# schematic_easyeda.net
KiCad netlist of a schematic drawn in EasyEDA
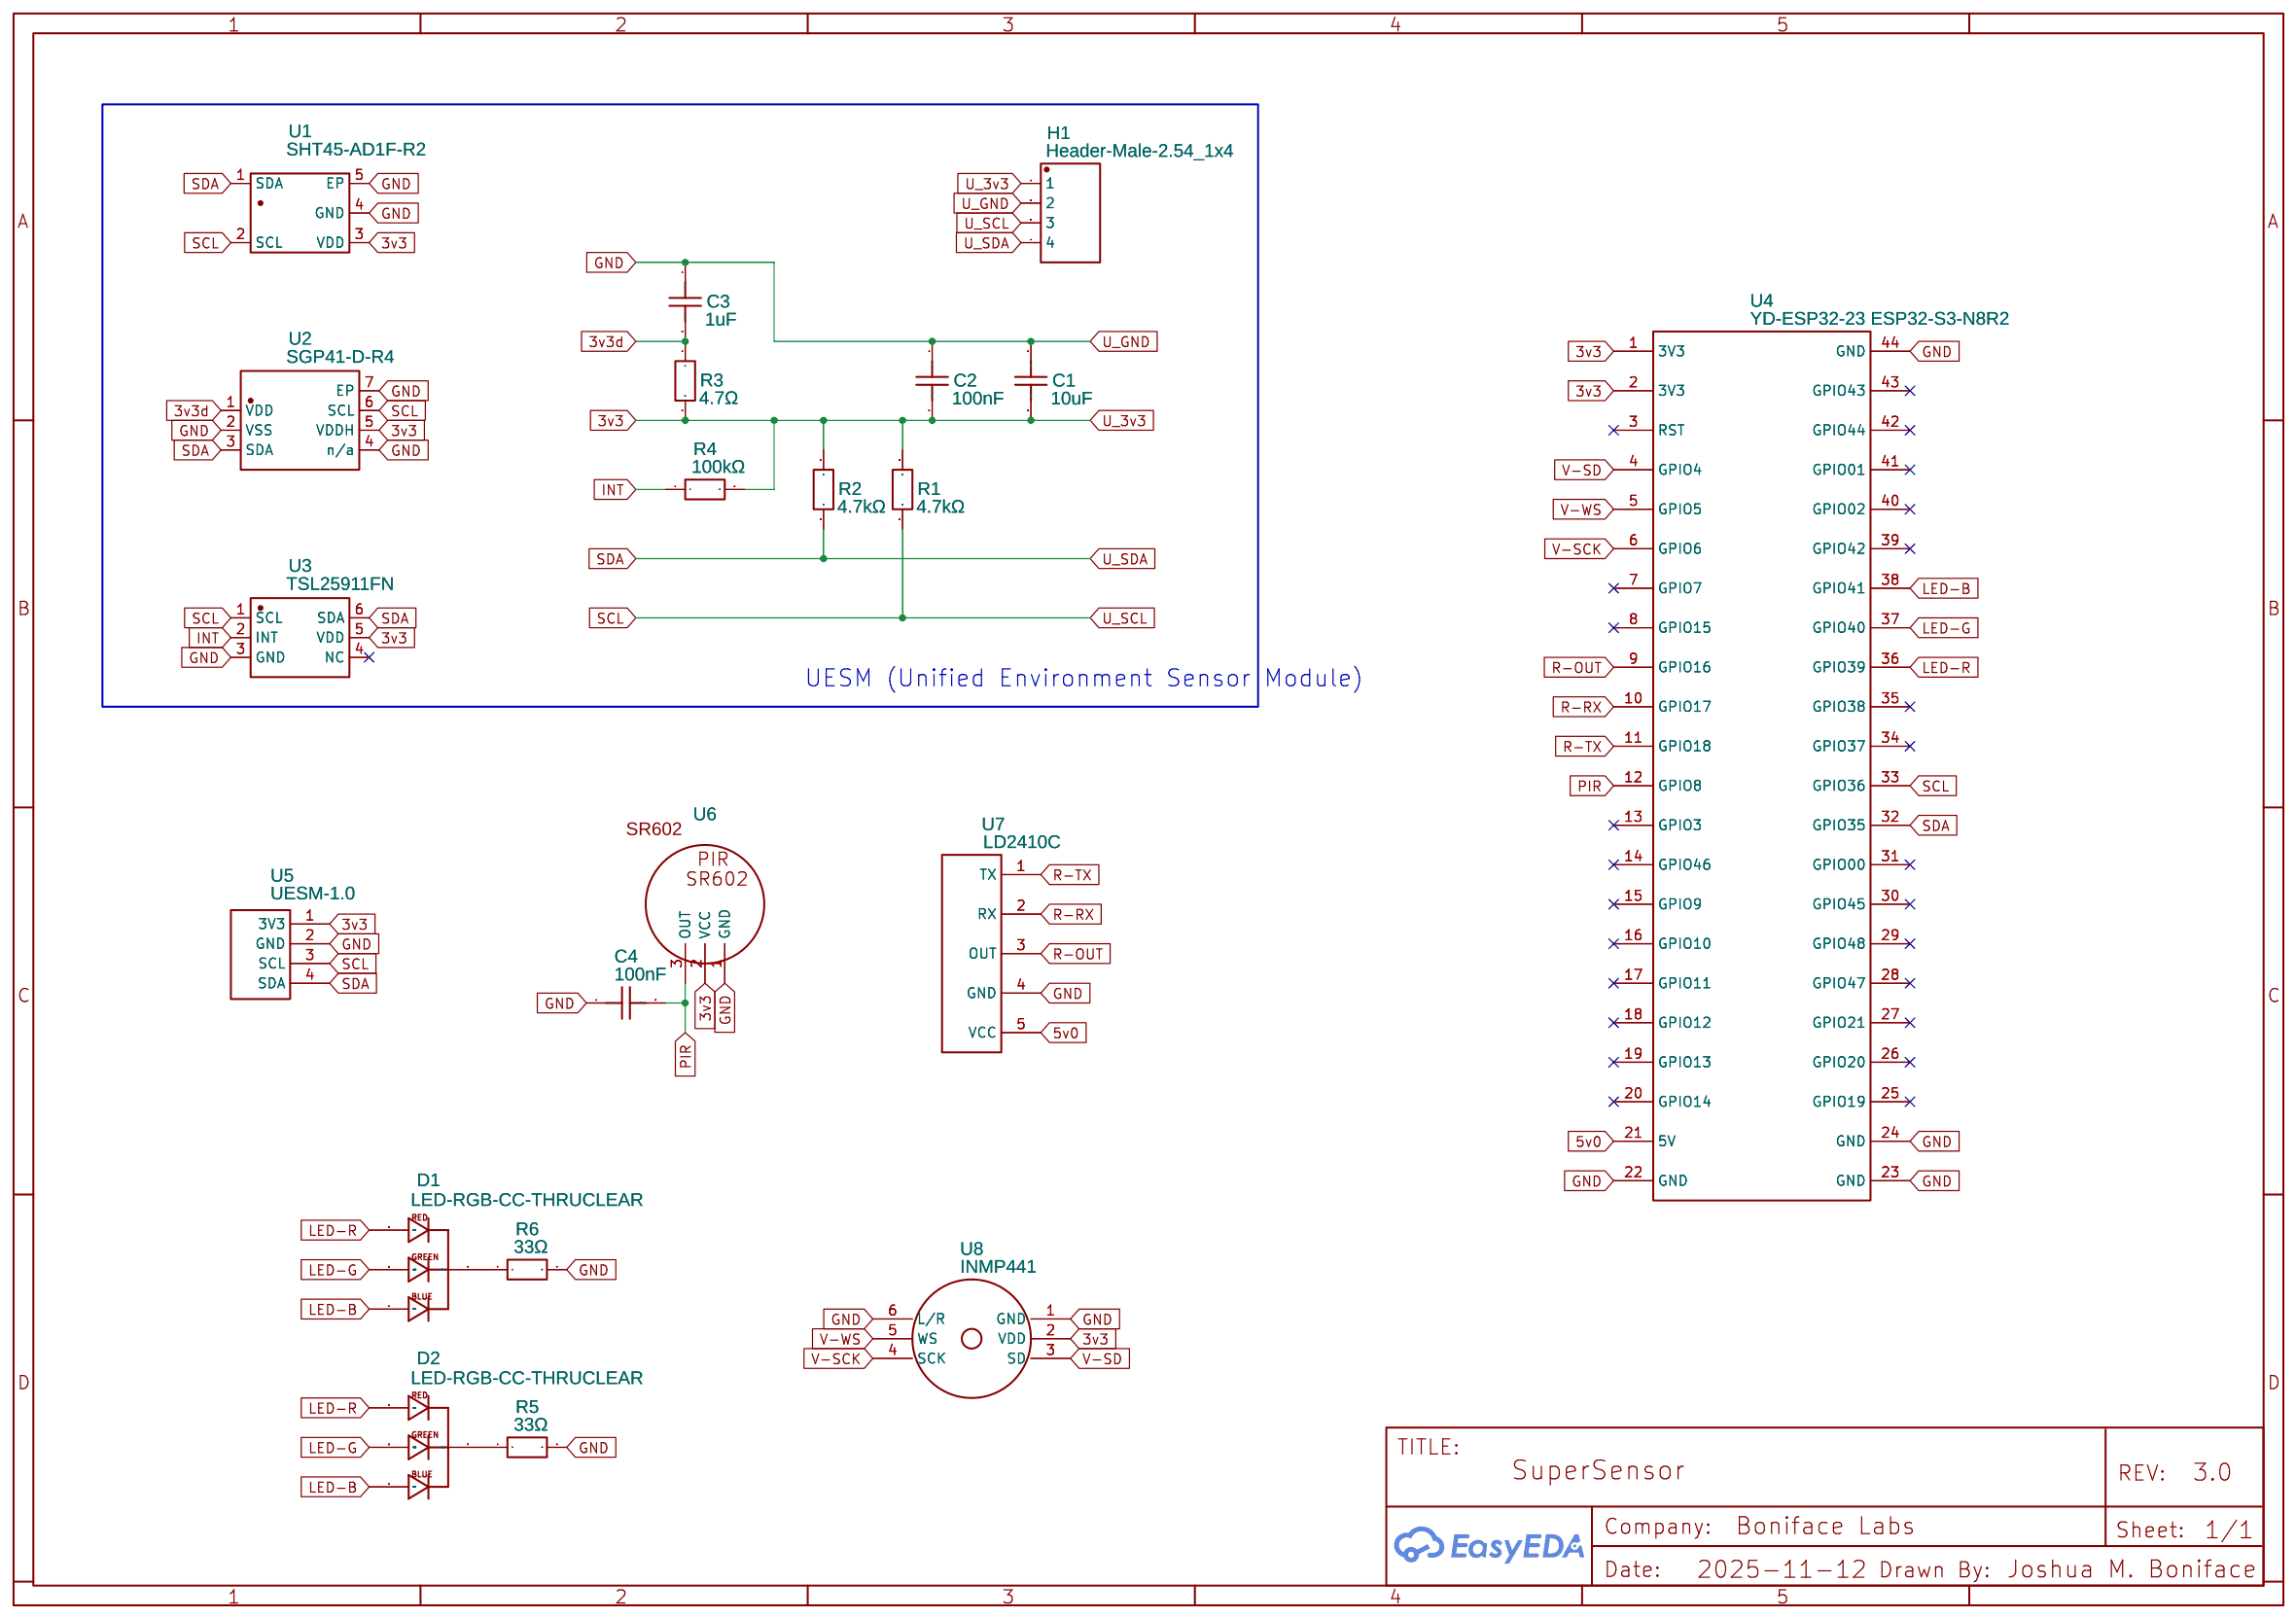
[diagram p0: schematic sheet]

(export (version "E")
  (design (tool "Eeschema 10.0.6"))
  (components
    (comp (ref "C1")
      (value "10uF")
      (fields (field (name "Manufacturer Part") "C2012JB1C106K125AB") (field (name "Manufacturer") "TDK"))
      (libsource (lib "") (part "C2012JB1C106K125AB"))
    )
    (comp (ref "C2")
      (value "100nF")
      (fields (field (name "Manufacturer Part") "C2012JB2A104K125AA") (field (name "Manufacturer") "TDK"))
      (libsource (lib "") (part "C2012JB2A104K125AA"))
    )
    (comp (ref "C3")
      (value "1uF")
      (fields (field (name "Manufacturer Part") "C2012X5R1E105K085AC") (field (name "Manufacturer") "TDK"))
      (libsource (lib "") (part "C2012X5R1E105K085AC"))
    )
    (comp (ref "C4")
      (value "100nF")
      (fields (field (name "Manufacturer Part") "C2012JB2A104K125AA") (field (name "Manufacturer") "TDK"))
      (libsource (lib "") (part "C2012JB2A104K125AA_1"))
    )
    (comp (ref "D1") (value "LED-RGB-CC-THRUCLEAR") (libsource (lib "") (part "LED-RGB-CC-THRUCLEAR")))
    (comp (ref "D2") (value "LED-RGB-CC-THRUCLEAR") (libsource (lib "") (part "LED-RGB-CC-THRUCLEAR")))
    (comp (ref "H1")
      (value "Header-Male-2.54_1x4")
      (fields (field (name "Manufacturer Part") "B-2100S04P-A110") (field (name "Manufacturer") "Ckmtw(灿科盟)"))
      (libsource (lib "") (part "Header-Male-2.54_1x4"))
    )
    (comp (ref "R1")
      (value "4.7kΩ")
      (fields
        (field (name "Manufacturer Part") "CRGP1206F4K7")
        (field (name "Manufacturer") "TE Connectivity(泰科电子)")
      )
      (libsource (lib "") (part "CRGP1206F4K7"))
    )
    (comp (ref "R2")
      (value "4.7kΩ")
      (fields
        (field (name "Manufacturer Part") "CRGP1206F4K7")
        (field (name "Manufacturer") "TE Connectivity(泰科电子)")
      )
      (libsource (lib "") (part "CRGP1206F4K7"))
    )
    (comp (ref "R3")
      (value "4.7Ω")
      (fields
        (field (name "Manufacturer Part") "CRGP1206F4K7")
        (field (name "Manufacturer") "TE Connectivity(泰科电子)")
      )
      (libsource (lib "") (part "CRGP1206F4K7"))
    )
    (comp (ref "R4")
      (value "100kΩ")
      (fields (field (name "Manufacturer Part") "WF06H1003BTL") (field (name "Manufacturer") "Walsin(华新科)"))
      (libsource (lib "") (part "WF06H1003BTL"))
    )
    (comp (ref "R5")
      (value "33Ω")
      (fields
        (field (name "Manufacturer Part") "CRGP1206F4K7")
        (field (name "Manufacturer") "TE Connectivity(泰科电子)")
      )
      (libsource (lib "") (part "CRGP1206F4K7_1"))
    )
    (comp (ref "R6")
      (value "33Ω")
      (fields
        (field (name "Manufacturer Part") "CRGP1206F4K7")
        (field (name "Manufacturer") "TE Connectivity(泰科电子)")
      )
      (libsource (lib "") (part "CRGP1206F4K7_1"))
    )
    (comp (ref "U1")
      (value "SHT45-AD1F-R2")
      (fields (field (name "Manufacturer") "Sensirion(瑞士盛思锐)"))
      (libsource (lib "") (part "SHT45-AD1F-R2"))
    )
    (comp (ref "U2")
      (value "SGP41-D-R4")
      (fields (field (name "Manufacturer") "Sensirion(瑞士盛思锐)"))
      (libsource (lib "") (part "SGP41-D-R4"))
    )
    (comp (ref "U3")
      (value "TSL25911FN")
      (fields (field (name "Manufacturer") "ams(艾迈斯半导体)"))
      (libsource (lib "") (part "TSL25911FN"))
    )
    (comp (ref "U4")
      (value "YD-ESP32-23 ESP32-S3-N8R2")
      (libsource (lib "") (part "YD-ESP32-23 ESP32-S3-N16R8 REALSIZE AHRS"))
    )
    (comp (ref "U5") (value "UESM-1.0") (libsource (lib "") (part "UESM-1.0")))
    (comp (ref "U6") (value "PIRSR602") (libsource (lib "") (part "PIRSR602")))
    (comp (ref "U7") (value "LD2410C") (libsource (lib "") (part "HLK-LD2410C WITH PCB")))
    (comp (ref "U8") (value "INMP441") (libsource (lib "") (part "INMP441-MEMS-I2S-MIC-MODULE")))
  )
  (nets
    (net (code "1") (name "3v3") (class "Default")
      (node (ref "C1") (pin "2") (pinfunction "2_2") (pintype "unspecified"))
      (node (ref "C2") (pin "2") (pinfunction "2_2") (pintype "unspecified"))
      (node (ref "H1") (pin "1") (pinfunction "1_1") (pintype "unspecified"))
      (node (ref "R1") (pin "1") (pinfunction "1_1") (pintype "unspecified"))
      (node (ref "R2") (pin "1") (pinfunction "1_1") (pintype "unspecified"))
      (node (ref "R3") (pin "2") (pinfunction "2_2") (pintype "unspecified"))
      (node (ref "R4") (pin "2") (pinfunction "2_2") (pintype "unspecified"))
      (node (ref "U1") (pin "3") (pinfunction "VDD_3") (pintype "unspecified"))
      (node (ref "U2") (pin "5") (pinfunction "VDDH_5") (pintype "unspecified"))
      (node (ref "U3") (pin "5") (pinfunction "VDD_5") (pintype "unspecified"))
      (node (ref "U4") (pin "1") (pinfunction "3V3_1") (pintype "unspecified"))
      (node (ref "U4") (pin "2") (pinfunction "3V3_2") (pintype "unspecified"))
      (node (ref "U5") (pin "1") (pinfunction "3V3_1") (pintype "unspecified"))
      (node (ref "U6") (pin "2") (pinfunction "VCC_2") (pintype "unspecified"))
      (node (ref "U8") (pin "2") (pinfunction "VDD_2") (pintype "unspecified"))
    )
    (net (code "2") (name "3v3d") (class "Default")
      (node (ref "C3") (pin "2") (pinfunction "2_2") (pintype "unspecified"))
      (node (ref "R3") (pin "1") (pinfunction "1_1") (pintype "unspecified"))
      (node (ref "U2") (pin "1") (pinfunction "VDD_1") (pintype "unspecified"))
    )
    (net (code "3") (name "5v0") (class "Default")
      (node (ref "U4") (pin "21") (pinfunction "5V_21") (pintype "unspecified"))
      (node (ref "U7") (pin "5") (pinfunction "VCC_5") (pintype "unspecified"))
    )
    (net (code "4") (name "GND") (class "Default")
      (node (ref "C1") (pin "1") (pinfunction "1_1") (pintype "unspecified"))
      (node (ref "C2") (pin "1") (pinfunction "1_1") (pintype "unspecified"))
      (node (ref "C3") (pin "1") (pinfunction "1_1") (pintype "unspecified"))
      (node (ref "C4") (pin "1") (pinfunction "1_1") (pintype "unspecified"))
      (node (ref "H1") (pin "2") (pinfunction "2_2") (pintype "unspecified"))
      (node (ref "R5") (pin "2") (pinfunction "2_2") (pintype "unspecified"))
      (node (ref "R6") (pin "2") (pinfunction "2_2") (pintype "unspecified"))
      (node (ref "U1") (pin "4") (pinfunction "GND_4") (pintype "unspecified"))
      (node (ref "U1") (pin "5") (pinfunction "EP_5") (pintype "unspecified"))
      (node (ref "U2") (pin "2") (pinfunction "VSS_2") (pintype "unspecified"))
      (node (ref "U2") (pin "4") (pinfunction "n/a_4") (pintype "unspecified"))
      (node (ref "U2") (pin "7") (pinfunction "EP_7") (pintype "unspecified"))
      (node (ref "U3") (pin "3") (pinfunction "GND_3") (pintype "unspecified"))
      (node (ref "U4") (pin "22") (pinfunction "GND_22") (pintype "unspecified"))
      (node (ref "U4") (pin "23") (pinfunction "GND_23") (pintype "unspecified"))
      (node (ref "U4") (pin "24") (pinfunction "GND_24") (pintype "unspecified"))
      (node (ref "U4") (pin "44") (pinfunction "GND_44") (pintype "unspecified"))
      (node (ref "U5") (pin "2") (pinfunction "GND_2") (pintype "unspecified"))
      (node (ref "U6") (pin "1") (pinfunction "GND_1") (pintype "unspecified"))
      (node (ref "U7") (pin "4") (pinfunction "GND_4") (pintype "unspecified"))
      (node (ref "U8") (pin "1") (pinfunction "GND_1") (pintype "unspecified"))
      (node (ref "U8") (pin "6") (pinfunction "L/R_6") (pintype "unspecified"))
    )
    (net (code "5") (name "INT") (class "Default")
      (node (ref "R4") (pin "1") (pinfunction "1_1") (pintype "unspecified"))
      (node (ref "U3") (pin "2") (pinfunction "INT_2") (pintype "unspecified"))
    )
    (net (code "6") (name "LED-B") (class "Default")
      (node (ref "D1") (pin "4") (pinfunction "BLUE_CATHODE_4") (pintype "unspecified"))
      (node (ref "D2") (pin "4") (pinfunction "BLUE_CATHODE_4") (pintype "unspecified"))
      (node (ref "U4") (pin "38") (pinfunction "GPIO41_38") (pintype "unspecified"))
    )
    (net (code "7") (name "LED-G") (class "Default")
      (node (ref "D1") (pin "3") (pinfunction "GREEN_CATHODE_3") (pintype "unspecified"))
      (node (ref "D2") (pin "3") (pinfunction "GREEN_CATHODE_3") (pintype "unspecified"))
      (node (ref "U4") (pin "37") (pinfunction "GPIO40_37") (pintype "unspecified"))
    )
    (net (code "8") (name "LED-R") (class "Default")
      (node (ref "D1") (pin "1") (pinfunction "RED_CATHODE_1") (pintype "unspecified"))
      (node (ref "D2") (pin "1") (pinfunction "RED_CATHODE_1") (pintype "unspecified"))
      (node (ref "U4") (pin "36") (pinfunction "GPIO39_36") (pintype "unspecified"))
    )
    (net (code "9") (name "Net-(D1-CATHODE)") (class "Default")
      (node (ref "D1") (pin "2") (pinfunction "CATHODE_2") (pintype "unspecified"))
      (node (ref "R6") (pin "1") (pinfunction "1_1") (pintype "unspecified"))
    )
    (net (code "10") (name "Net-(D2-CATHODE)") (class "Default")
      (node (ref "D2") (pin "2") (pinfunction "CATHODE_2") (pintype "unspecified"))
      (node (ref "R5") (pin "1") (pinfunction "1_1") (pintype "unspecified"))
    )
    (net (code "11") (name "PIR") (class "Default")
      (node (ref "C4") (pin "2") (pinfunction "2_2") (pintype "unspecified"))
      (node (ref "U4") (pin "12") (pinfunction "GPIO8_12") (pintype "unspecified"))
      (node (ref "U6") (pin "3") (pinfunction "OUT_3") (pintype "unspecified"))
    )
    (net (code "12") (name "R-OUT") (class "Default")
      (node (ref "U4") (pin "9") (pinfunction "GPIO16_9") (pintype "unspecified"))
      (node (ref "U7") (pin "3") (pinfunction "OUT_3") (pintype "unspecified"))
    )
    (net (code "13") (name "R-RX") (class "Default")
      (node (ref "U4") (pin "10") (pinfunction "GPIO17_10") (pintype "unspecified"))
      (node (ref "U7") (pin "2") (pinfunction "RX_2") (pintype "unspecified"))
    )
    (net (code "14") (name "R-TX") (class "Default")
      (node (ref "U4") (pin "11") (pinfunction "GPIO18_11") (pintype "unspecified"))
      (node (ref "U7") (pin "1") (pinfunction "TX_1") (pintype "unspecified"))
    )
    (net (code "15") (name "SCL") (class "Default")
      (node (ref "H1") (pin "3") (pinfunction "3_3") (pintype "unspecified"))
      (node (ref "R1") (pin "2") (pinfunction "2_2") (pintype "unspecified"))
      (node (ref "U1") (pin "2") (pinfunction "SCL_2") (pintype "unspecified"))
      (node (ref "U2") (pin "6") (pinfunction "SCL_6") (pintype "unspecified"))
      (node (ref "U3") (pin "1") (pinfunction "SCL_1") (pintype "unspecified"))
      (node (ref "U4") (pin "33") (pinfunction "GPIO36_33") (pintype "unspecified"))
      (node (ref "U5") (pin "3") (pinfunction "SCL_3") (pintype "unspecified"))
    )
    (net (code "16") (name "SDA") (class "Default")
      (node (ref "H1") (pin "4") (pinfunction "4_4") (pintype "unspecified"))
      (node (ref "R2") (pin "2") (pinfunction "2_2") (pintype "unspecified"))
      (node (ref "U1") (pin "1") (pinfunction "SDA_1") (pintype "unspecified"))
      (node (ref "U2") (pin "3") (pinfunction "SDA_3") (pintype "unspecified"))
      (node (ref "U3") (pin "6") (pinfunction "SDA_6") (pintype "unspecified"))
      (node (ref "U4") (pin "32") (pinfunction "GPIO35_32") (pintype "unspecified"))
      (node (ref "U5") (pin "4") (pinfunction "SDA_4") (pintype "unspecified"))
    )
    (net (code "17") (name "V-SCK") (class "Default")
      (node (ref "U4") (pin "6") (pinfunction "GPIO6_6") (pintype "unspecified"))
      (node (ref "U8") (pin "4") (pinfunction "SCK_4") (pintype "unspecified"))
    )
    (net (code "18") (name "V-SD") (class "Default")
      (node (ref "U4") (pin "4") (pinfunction "GPIO4_4") (pintype "unspecified"))
      (node (ref "U8") (pin "3") (pinfunction "SD_3") (pintype "unspecified"))
    )
    (net (code "19") (name "V-WS") (class "Default")
      (node (ref "U4") (pin "5") (pinfunction "GPIO5_5") (pintype "unspecified"))
      (node (ref "U8") (pin "5") (pinfunction "WS_5") (pintype "unspecified"))
    )
    (net (code "20") (name "unconnected-(U3-NC-Pad4)") (class "Default")
      (node (ref "U3") (pin "4") (pinfunction "NC_4") (pintype "unspecified+no_connect"))
    )
    (net (code "21") (name "unconnected-(U4-GPIO00-Pad31)") (class "Default")
      (node (ref "U4") (pin "31") (pinfunction "GPIO00_31") (pintype "unspecified+no_connect"))
    )
    (net (code "22") (name "unconnected-(U4-GPIO01-Pad41)") (class "Default")
      (node (ref "U4") (pin "41") (pinfunction "GPIO01_41") (pintype "unspecified+no_connect"))
    )
    (net (code "23") (name "unconnected-(U4-GPIO02-Pad40)") (class "Default")
      (node (ref "U4") (pin "40") (pinfunction "GPIO02_40") (pintype "unspecified+no_connect"))
    )
    (net (code "24") (name "unconnected-(U4-GPIO3-Pad13)") (class "Default")
      (node (ref "U4") (pin "13") (pinfunction "GPIO3_13") (pintype "unspecified+no_connect"))
    )
    (net (code "25") (name "unconnected-(U4-GPIO7-Pad7)") (class "Default")
      (node (ref "U4") (pin "7") (pinfunction "GPIO7_7") (pintype "unspecified+no_connect"))
    )
    (net (code "26") (name "unconnected-(U4-GPIO9-Pad15)") (class "Default")
      (node (ref "U4") (pin "15") (pinfunction "GPIO9_15") (pintype "unspecified+no_connect"))
    )
    (net (code "27") (name "unconnected-(U4-GPIO10-Pad16)") (class "Default")
      (node (ref "U4") (pin "16") (pinfunction "GPIO10_16") (pintype "unspecified+no_connect"))
    )
    (net (code "28") (name "unconnected-(U4-GPIO11-Pad17)") (class "Default")
      (node (ref "U4") (pin "17") (pinfunction "GPIO11_17") (pintype "unspecified+no_connect"))
    )
    (net (code "29") (name "unconnected-(U4-GPIO12-Pad18)") (class "Default")
      (node (ref "U4") (pin "18") (pinfunction "GPIO12_18") (pintype "unspecified+no_connect"))
    )
    (net (code "30") (name "unconnected-(U4-GPIO13-Pad19)") (class "Default")
      (node (ref "U4") (pin "19") (pinfunction "GPIO13_19") (pintype "unspecified+no_connect"))
    )
    (net (code "31") (name "unconnected-(U4-GPIO14-Pad20)") (class "Default")
      (node (ref "U4") (pin "20") (pinfunction "GPIO14_20") (pintype "unspecified+no_connect"))
    )
    (net (code "32") (name "unconnected-(U4-GPIO15-Pad8)") (class "Default")
      (node (ref "U4") (pin "8") (pinfunction "GPIO15_8") (pintype "unspecified+no_connect"))
    )
    (net (code "33") (name "unconnected-(U4-GPIO19-Pad25)") (class "Default")
      (node (ref "U4") (pin "25") (pinfunction "GPIO19_25") (pintype "unspecified+no_connect"))
    )
    (net (code "34") (name "unconnected-(U4-GPIO20-Pad26)") (class "Default")
      (node (ref "U4") (pin "26") (pinfunction "GPIO20_26") (pintype "unspecified+no_connect"))
    )
    (net (code "35") (name "unconnected-(U4-GPIO21-Pad27)") (class "Default")
      (node (ref "U4") (pin "27") (pinfunction "GPIO21_27") (pintype "unspecified+no_connect"))
    )
    (net (code "36") (name "unconnected-(U4-GPIO37-Pad34)") (class "Default")
      (node (ref "U4") (pin "34") (pinfunction "GPIO37_34") (pintype "unspecified+no_connect"))
    )
    (net (code "37") (name "unconnected-(U4-GPIO38-Pad35)") (class "Default")
      (node (ref "U4") (pin "35") (pinfunction "GPIO38_35") (pintype "unspecified+no_connect"))
    )
    (net (code "38") (name "unconnected-(U4-GPIO42-Pad39)") (class "Default")
      (node (ref "U4") (pin "39") (pinfunction "GPIO42_39") (pintype "unspecified+no_connect"))
    )
    (net (code "39") (name "unconnected-(U4-GPIO43-Pad43)") (class "Default")
      (node (ref "U4") (pin "43") (pinfunction "GPIO43_43") (pintype "unspecified+no_connect"))
    )
    (net (code "40") (name "unconnected-(U4-GPIO44-Pad42)") (class "Default")
      (node (ref "U4") (pin "42") (pinfunction "GPIO44_42") (pintype "unspecified+no_connect"))
    )
    (net (code "41") (name "unconnected-(U4-GPIO45-Pad30)") (class "Default")
      (node (ref "U4") (pin "30") (pinfunction "GPIO45_30") (pintype "unspecified+no_connect"))
    )
    (net (code "42") (name "unconnected-(U4-GPIO46-Pad14)") (class "Default")
      (node (ref "U4") (pin "14") (pinfunction "GPIO46_14") (pintype "unspecified+no_connect"))
    )
    (net (code "43") (name "unconnected-(U4-GPIO47-Pad28)") (class "Default")
      (node (ref "U4") (pin "28") (pinfunction "GPIO47_28") (pintype "unspecified+no_connect"))
    )
    (net (code "44") (name "unconnected-(U4-GPIO48-Pad29)") (class "Default")
      (node (ref "U4") (pin "29") (pinfunction "GPIO48_29") (pintype "unspecified+no_connect"))
    )
    (net (code "45") (name "unconnected-(U4-RST-Pad3)") (class "Default")
      (node (ref "U4") (pin "3") (pinfunction "RST_3") (pintype "unspecified+no_connect"))
    )
  )
)
